# Power_Regulation.net
KiCad netlist of a schematic drawn in Altium Designer
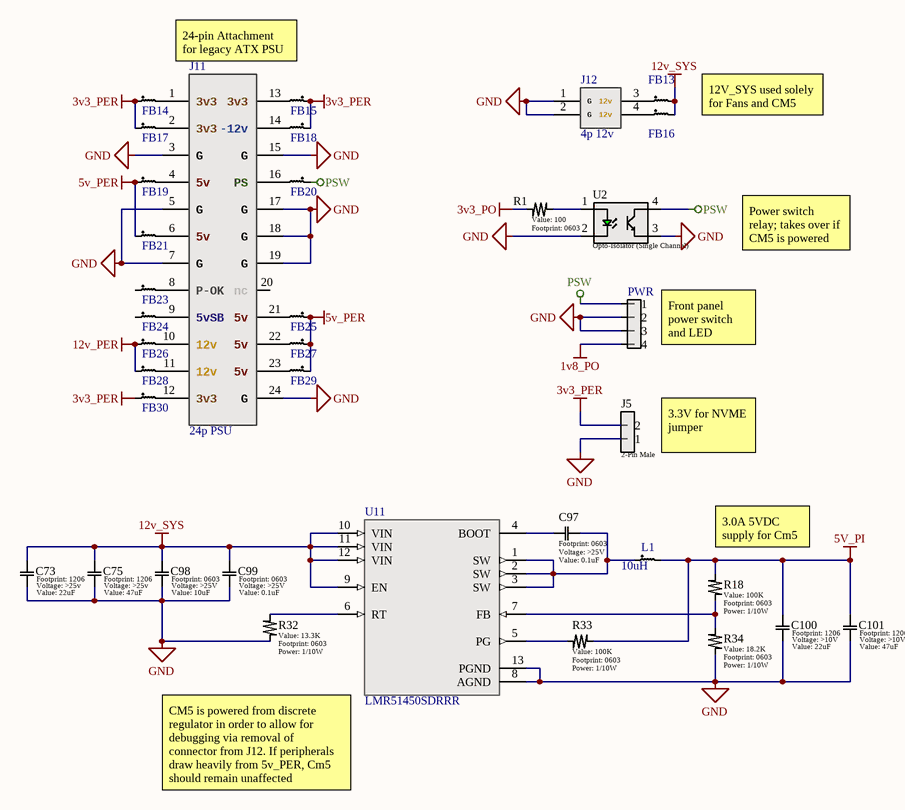
[diagram p0: Power_Regulation.SchDoc]

(export (version "E")
  (design (tool "Eeschema 10.0.6"))
  (components
    (comp (ref "C73")
      (value "22uF")
      (footprint "1206")
      (fields
        (field (name "VOLTAGE") ">25v")
        (field (name "TOLERANCE") "20%")
        (field (name "Comment") "Generic Capacitor")
      )
      (libsource (lib "Capacitors") (part "Generic Capacitor"))
    )
    (comp (ref "C75")
      (value "47uF")
      (footprint "1206")
      (fields
        (field (name "VOLTAGE") ">25v")
        (field (name "TOLERANCE") "20%")
        (field (name "Comment") "Generic Capacitor")
      )
      (libsource (lib "Capacitors") (part "Generic Capacitor"))
    )
    (comp (ref "C97")
      (value "0.1uF")
      (footprint "0603")
      (fields
        (field (name "VOLTAGE") ">25V")
        (field (name "TOLERANCE") "10%")
        (field (name "Comment") "Generic Capacitor")
      )
      (libsource (lib "Capacitors") (part "Generic Capacitor"))
    )
    (comp (ref "C98")
      (value "10uF")
      (footprint "0603")
      (fields
        (field (name "VOLTAGE") ">25V")
        (field (name "TOLERANCE") "10%")
        (field (name "Comment") "Generic Capacitor")
      )
      (libsource (lib "Capacitors") (part "Generic Capacitor"))
    )
    (comp (ref "C99")
      (value "0.1uF")
      (footprint "0603")
      (fields
        (field (name "VOLTAGE") ">25V")
        (field (name "TOLERANCE") "10%")
        (field (name "Comment") "Generic Capacitor")
      )
      (libsource (lib "Capacitors") (part "Generic Capacitor"))
    )
    (comp (ref "C100")
      (value "22uF")
      (footprint "1206")
      (fields
        (field (name "VOLTAGE") ">10V")
        (field (name "TOLERANCE") "20%")
        (field (name "Comment") "Generic Capacitor")
      )
      (libsource (lib "Capacitors") (part "Generic Capacitor"))
    )
    (comp (ref "C101")
      (value "47uF")
      (footprint "1206")
      (fields
        (field (name "VOLTAGE") ">10V")
        (field (name "TOLERANCE") "10%")
        (field (name "Comment") "Generic Capacitor")
      )
      (libsource (lib "Capacitors") (part "Generic Capacitor"))
    )
    (comp (ref "FB13")
      (value "1206 Ferrite")
      (footprint "1206")
      (description "160 Ohms @ 100MHz 1 Power, Signal Line Ferrite Bead 1206 (3216 Metric) 6A 18mOhm")
      (libsource (lib "Inductors") (part "HI1206T161R-10"))
    )
    (comp (ref "FB14")
      (value "1206 Ferrite")
      (footprint "1206")
      (description "160 Ohms @ 100MHz 1 Power, Signal Line Ferrite Bead 1206 (3216 Metric) 6A 18mOhm")
      (libsource (lib "Inductors") (part "HI1206T161R-10"))
    )
    (comp (ref "FB15")
      (value "1206 Ferrite")
      (footprint "1206")
      (description "160 Ohms @ 100MHz 1 Power, Signal Line Ferrite Bead 1206 (3216 Metric) 6A 18mOhm")
      (libsource (lib "") (part "HI1206T161R-10_1"))
    )
    (comp (ref "FB16")
      (value "1206 Ferrite")
      (footprint "1206")
      (description "160 Ohms @ 100MHz 1 Power, Signal Line Ferrite Bead 1206 (3216 Metric) 6A 18mOhm")
      (libsource (lib "Inductors") (part "HI1206T161R-10"))
    )
    (comp (ref "FB17")
      (value "1206 Ferrite")
      (footprint "1206")
      (description "160 Ohms @ 100MHz 1 Power, Signal Line Ferrite Bead 1206 (3216 Metric) 6A 18mOhm")
      (libsource (lib "Inductors") (part "HI1206T161R-10"))
    )
    (comp (ref "FB18")
      (value "1206 Ferrite")
      (footprint "1206")
      (description "160 Ohms @ 100MHz 1 Power, Signal Line Ferrite Bead 1206 (3216 Metric) 6A 18mOhm")
      (libsource (lib "") (part "HI1206T161R-10_1"))
    )
    (comp (ref "FB19")
      (value "1206 Ferrite")
      (footprint "1206")
      (description "160 Ohms @ 100MHz 1 Power, Signal Line Ferrite Bead 1206 (3216 Metric) 6A 18mOhm")
      (libsource (lib "Inductors") (part "HI1206T161R-10"))
    )
    (comp (ref "FB20")
      (value "1206 Ferrite")
      (footprint "1206")
      (description "160 Ohms @ 100MHz 1 Power, Signal Line Ferrite Bead 1206 (3216 Metric) 6A 18mOhm")
      (libsource (lib "") (part "HI1206T161R-10_1"))
    )
    (comp (ref "FB21")
      (value "1206 Ferrite")
      (footprint "1206")
      (description "160 Ohms @ 100MHz 1 Power, Signal Line Ferrite Bead 1206 (3216 Metric) 6A 18mOhm")
      (libsource (lib "Inductors") (part "HI1206T161R-10"))
    )
    (comp (ref "FB23")
      (value "1206 Ferrite")
      (footprint "1206")
      (description "160 Ohms @ 100MHz 1 Power, Signal Line Ferrite Bead 1206 (3216 Metric) 6A 18mOhm")
      (libsource (lib "Inductors") (part "HI1206T161R-10"))
    )
    (comp (ref "FB24")
      (value "1206 Ferrite")
      (footprint "1206")
      (description "160 Ohms @ 100MHz 1 Power, Signal Line Ferrite Bead 1206 (3216 Metric) 6A 18mOhm")
      (libsource (lib "Inductors") (part "HI1206T161R-10"))
    )
    (comp (ref "FB25")
      (value "1206 Ferrite")
      (footprint "1206")
      (description "160 Ohms @ 100MHz 1 Power, Signal Line Ferrite Bead 1206 (3216 Metric) 6A 18mOhm")
      (libsource (lib "") (part "HI1206T161R-10_1"))
    )
    (comp (ref "FB26")
      (value "1206 Ferrite")
      (footprint "1206")
      (description "160 Ohms @ 100MHz 1 Power, Signal Line Ferrite Bead 1206 (3216 Metric) 6A 18mOhm")
      (libsource (lib "Inductors") (part "HI1206T161R-10"))
    )
    (comp (ref "FB27")
      (value "1206 Ferrite")
      (footprint "1206")
      (description "160 Ohms @ 100MHz 1 Power, Signal Line Ferrite Bead 1206 (3216 Metric) 6A 18mOhm")
      (libsource (lib "") (part "HI1206T161R-10_1"))
    )
    (comp (ref "FB28")
      (value "1206 Ferrite")
      (footprint "1206")
      (description "160 Ohms @ 100MHz 1 Power, Signal Line Ferrite Bead 1206 (3216 Metric) 6A 18mOhm")
      (libsource (lib "Inductors") (part "HI1206T161R-10"))
    )
    (comp (ref "FB29")
      (value "1206 Ferrite")
      (footprint "1206")
      (description "160 Ohms @ 100MHz 1 Power, Signal Line Ferrite Bead 1206 (3216 Metric) 6A 18mOhm")
      (libsource (lib "") (part "HI1206T161R-10_1"))
    )
    (comp (ref "FB30")
      (value "1206 Ferrite")
      (footprint "1206")
      (description "160 Ohms @ 100MHz 1 Power, Signal Line Ferrite Bead 1206 (3216 Metric) 6A 18mOhm")
      (libsource (lib "Inductors") (part "HI1206T161R-10"))
    )
    (comp (ref "J5")
      (value "2-Pin Male")
      (footprint "0022057025")
      (description "Conn Shrouded Header (4 Sides) HDR 2 POS 2.5mm Solder RA Thru-Hole SPOX™ Bag")
      (libsource (lib "Connectors") (part "0022057025"))
    )
    (comp (ref "J11")
      (value "24p PSU")
      (footprint "CONN_442060007_MOL")
      (description "Connector Header Through Hole 24 position 0.165\" (4.20mm)")
      (libsource (lib "Connectors") (part "442060007"))
    )
    (comp (ref "J12")
      (value "4p 12v")
      (footprint "CON_39281043")
      (description "Connector Header Through Hole 4 position 0.165\" (4.20mm)")
      (libsource (lib "Connectors") (part "39281043"))
    )
    (comp (ref "L1")
      (value "10uH")
      (footprint "SMD 8.2x8.6mm")
      (description "5.1A 10uH ±20% 5.2A - Power Inductor")
      (fields
        (field (name "MANUFACTURER_PART_NUMBER") "IHLP3232DZER100M5A")
        (field (name "COPYRIGHT") "Copyright (C) 2023 Ultra Librarian. All rights reserved.")
      )
      (libsource (lib "Inductors") (part "IHLP3232DZER100M5A"))
    )
    (comp (ref "PWR")
      (value "4-Pin Male Header (0.100\" Pitch)")
      (footprint "TSW-104-07-T-S")
      (description "Connector Header Through Hole 4 position 0.100\" (2.54mm)")
      (libsource (lib "Connectors") (part "TSW-104-07-T-S"))
    )
    (comp (ref "R1")
      (value "100")
      (footprint "0603")
      (fields
        (field (name "TOLERANCE") "1%")
        (field (name "POWER") "1/10W")
        (field (name "Comment") "Generic Resistor")
      )
      (libsource (lib "Resistors") (part "Generic Resistor"))
    )
    (comp (ref "R18")
      (value "100K")
      (footprint "0603")
      (fields
        (field (name "TOLERANCE") "1%")
        (field (name "POWER") "1/10W")
        (field (name "Comment") "Generic Resistor")
      )
      (libsource (lib "Resistors") (part "Generic Resistor"))
    )
    (comp (ref "R32")
      (value "13.3K")
      (footprint "0603")
      (fields
        (field (name "TOLERANCE") "1%")
        (field (name "POWER") "1/10W")
        (field (name "Comment") "Generic Resistor")
      )
      (libsource (lib "Resistors") (part "Generic Resistor"))
    )
    (comp (ref "R33")
      (value "100K")
      (footprint "0603")
      (fields
        (field (name "TOLERANCE") "1%")
        (field (name "POWER") "1/10W")
        (field (name "Comment") "Generic Resistor")
      )
      (libsource (lib "Resistors") (part "Generic Resistor"))
    )
    (comp (ref "R34")
      (value "18.2K")
      (footprint "0603")
      (fields
        (field (name "TOLERANCE") "1%")
        (field (name "POWER") "1/10W")
        (field (name "Comment") "Generic Resistor")
      )
      (libsource (lib "Resistors") (part "Generic Resistor"))
    )
    (comp (ref "U2")
      (value "Opto-Isolator (Single Channel)")
      (footprint "4-SMD (7.62mm Gull-Wing) Opto-Transistor")
      (description "LTV Series Single Channel 80 V 5000 Vrms Transistor Output Optocoupler SMT-DIP-4")
      (fields
        (field (name "MANUFACTURER") "Vishay Lite-On")
        (field (name "MANUFACTURER PART NUMBER") "LTV-816S-TA1")
      )
      (libsource (lib "Switches") (part "LTV-816S"))
    )
    (comp (ref "U11")
      (value "LMR51450SDRRR")
      (footprint "WSON-12")
      (description "36-V, 5-A synchronous buck converter")
      (fields (field (name "MF") "Texas Instruments"))
      (libsource (lib "Regulators") (part "LMR51450SDRRR"))
    )
  )
  (nets
    (net (code "1") (name "1v8_PO") (class "Default")
      (node (ref "PWR") (pin "4") (pinfunction "4_4") (pintype "passive"))
    )
    (net (code "2") (name "3v3_PER") (class "Default")
      (node (ref "FB14") (pin "1") (pinfunction "1_1") (pintype "passive"))
      (node (ref "FB15") (pin "1") (pinfunction "1_1") (pintype "passive"))
      (node (ref "FB17") (pin "1") (pinfunction "1_1") (pintype "passive"))
      (node (ref "FB18") (pin "1") (pinfunction "1_1") (pintype "passive"))
      (node (ref "FB30") (pin "1") (pinfunction "1_1") (pintype "passive"))
      (node (ref "J5") (pin "2") (pinfunction "2_2") (pintype "passive"))
    )
    (net (code "3") (name "3v3_PO") (class "Default")
      (node (ref "R1") (pin "1") (pinfunction "1_1") (pintype "passive"))
    )
    (net (code "4") (name "5V_PI") (class "Default")
      (node (ref "C100") (pin "1") (pinfunction "1_1") (pintype "passive"))
      (node (ref "C101") (pin "1") (pinfunction "1_1") (pintype "passive"))
      (node (ref "L1") (pin "2") (pinfunction "2_2") (pintype "passive"))
      (node (ref "R18") (pin "2") (pinfunction "2_2") (pintype "passive"))
      (node (ref "R33") (pin "1") (pinfunction "1_1") (pintype "passive"))
    )
    (net (code "5") (name "5v_PER") (class "Default")
      (node (ref "FB19") (pin "1") (pinfunction "1_1") (pintype "passive"))
      (node (ref "FB21") (pin "1") (pinfunction "1_1") (pintype "passive"))
      (node (ref "FB25") (pin "1") (pinfunction "1_1") (pintype "passive"))
      (node (ref "FB27") (pin "1") (pinfunction "1_1") (pintype "passive"))
      (node (ref "FB29") (pin "1") (pinfunction "1_1") (pintype "passive"))
    )
    (net (code "6") (name "12v_PER") (class "Default")
      (node (ref "FB26") (pin "1") (pinfunction "1_1") (pintype "passive"))
      (node (ref "FB28") (pin "1") (pinfunction "1_1") (pintype "passive"))
    )
    (net (code "7") (name "12v_SYS") (class "Default")
      (node (ref "C73") (pin "1") (pinfunction "1_1") (pintype "passive"))
      (node (ref "C75") (pin "1") (pinfunction "1_1") (pintype "passive"))
      (node (ref "C98") (pin "1") (pinfunction "1_1") (pintype "passive"))
      (node (ref "C99") (pin "1") (pinfunction "1_1") (pintype "passive"))
      (node (ref "FB13") (pin "2") (pinfunction "2_2") (pintype "passive"))
      (node (ref "FB16") (pin "2") (pinfunction "2_2") (pintype "passive"))
      (node (ref "U11") (pin "10") (pinfunction "VIN_10") (pintype "input"))
      (node (ref "U11") (pin "11") (pinfunction "VIN_11") (pintype "input"))
      (node (ref "U11") (pin "12") (pinfunction "VIN_12") (pintype "input"))
      (node (ref "U11") (pin "9") (pinfunction "EN_9") (pintype "input"))
    )
    (net (code "8") (name "GND") (class "Default")
      (node (ref "C100") (pin "2") (pinfunction "2_2") (pintype "passive"))
      (node (ref "C101") (pin "2") (pinfunction "2_2") (pintype "passive"))
      (node (ref "C73") (pin "2") (pinfunction "2_2") (pintype "passive"))
      (node (ref "C75") (pin "2") (pinfunction "2_2") (pintype "passive"))
      (node (ref "C98") (pin "2") (pinfunction "2_2") (pintype "passive"))
      (node (ref "C99") (pin "2") (pinfunction "2_2") (pintype "passive"))
      (node (ref "J11") (pin "15") (pinfunction "G_15") (pintype "passive"))
      (node (ref "J11") (pin "17") (pinfunction "G_17") (pintype "passive"))
      (node (ref "J11") (pin "18") (pinfunction "G_18") (pintype "passive"))
      (node (ref "J11") (pin "19") (pinfunction "G_19") (pintype "passive"))
      (node (ref "J11") (pin "24") (pinfunction "G_24") (pintype "passive"))
      (node (ref "J11") (pin "3") (pinfunction "G_3") (pintype "passive"))
      (node (ref "J11") (pin "5") (pinfunction "G_5") (pintype "passive"))
      (node (ref "J11") (pin "7") (pinfunction "G_7") (pintype "passive"))
      (node (ref "J12") (pin "1") (pinfunction "G_1") (pintype "passive"))
      (node (ref "J12") (pin "2") (pinfunction "G_2") (pintype "passive"))
      (node (ref "J5") (pin "1") (pinfunction "1_1") (pintype "passive"))
      (node (ref "PWR") (pin "2") (pinfunction "2_2") (pintype "passive"))
      (node (ref "PWR") (pin "3") (pinfunction "3_3") (pintype "passive"))
      (node (ref "R32") (pin "1") (pinfunction "1_1") (pintype "passive"))
      (node (ref "R34") (pin "1") (pinfunction "1_1") (pintype "passive"))
      (node (ref "U11") (pin "13") (pinfunction "PGND_13") (pintype "power_in"))
      (node (ref "U11") (pin "8") (pinfunction "AGND_8") (pintype "power_in"))
      (node (ref "U2") (pin "2") (pinfunction "2_2") (pintype "passive"))
      (node (ref "U2") (pin "3") (pinfunction "3_3") (pintype "passive"))
    )
    (net (code "9") (name "Net-(C97-Pad2)") (class "Default")
      (node (ref "C97") (pin "2") (pinfunction "2_2") (pintype "passive"))
      (node (ref "L1") (pin "1") (pinfunction "1_1") (pintype "passive"))
      (node (ref "U11") (pin "1") (pinfunction "SW_1") (pintype "output"))
      (node (ref "U11") (pin "2") (pinfunction "SW_2") (pintype "output"))
      (node (ref "U11") (pin "3") (pinfunction "SW_3") (pintype "output"))
    )
    (net (code "10") (name "Net-(FB13-Pad1)") (class "Default")
      (node (ref "FB13") (pin "1") (pinfunction "1_1") (pintype "passive"))
      (node (ref "J12") (pin "3") (pinfunction "12v_3") (pintype "passive"))
    )
    (net (code "11") (name "Net-(FB14-Pad2)") (class "Default")
      (node (ref "FB14") (pin "2") (pinfunction "2_2") (pintype "passive"))
      (node (ref "J11") (pin "1") (pinfunction "3v3_1") (pintype "passive"))
    )
    (net (code "12") (name "Net-(FB15-Pad2)") (class "Default")
      (node (ref "FB15") (pin "2") (pinfunction "2_2") (pintype "passive"))
      (node (ref "J11") (pin "13") (pinfunction "3v3_13") (pintype "passive"))
    )
    (net (code "13") (name "Net-(FB16-Pad1)") (class "Default")
      (node (ref "FB16") (pin "1") (pinfunction "1_1") (pintype "passive"))
      (node (ref "J12") (pin "4") (pinfunction "12v_4") (pintype "passive"))
    )
    (net (code "14") (name "Net-(FB17-Pad2)") (class "Default")
      (node (ref "FB17") (pin "2") (pinfunction "2_2") (pintype "passive"))
      (node (ref "J11") (pin "2") (pinfunction "3v3_2") (pintype "passive"))
    )
    (net (code "15") (name "Net-(FB19-Pad2)") (class "Default")
      (node (ref "FB19") (pin "2") (pinfunction "2_2") (pintype "passive"))
      (node (ref "J11") (pin "4") (pinfunction "5v_4") (pintype "passive"))
    )
    (net (code "16") (name "Net-(FB21-Pad2)") (class "Default")
      (node (ref "FB21") (pin "2") (pinfunction "2_2") (pintype "passive"))
      (node (ref "J11") (pin "6") (pinfunction "5v_6") (pintype "passive"))
    )
    (net (code "17") (name "Net-(FB25-Pad2)") (class "Default")
      (node (ref "FB25") (pin "2") (pinfunction "2_2") (pintype "passive"))
      (node (ref "J11") (pin "21") (pinfunction "5v_21") (pintype "passive"))
    )
    (net (code "18") (name "Net-(FB26-Pad2)") (class "Default")
      (node (ref "FB26") (pin "2") (pinfunction "2_2") (pintype "passive"))
      (node (ref "J11") (pin "10") (pinfunction "12v_10") (pintype "passive"))
    )
    (net (code "19") (name "Net-(FB27-Pad2)") (class "Default")
      (node (ref "FB27") (pin "2") (pinfunction "2_2") (pintype "passive"))
      (node (ref "J11") (pin "22") (pinfunction "5v_22") (pintype "passive"))
    )
    (net (code "20") (name "Net-(FB28-Pad2)") (class "Default")
      (node (ref "FB28") (pin "2") (pinfunction "2_2") (pintype "passive"))
      (node (ref "J11") (pin "11") (pinfunction "12v_11") (pintype "passive"))
    )
    (net (code "21") (name "Net-(FB29-Pad2)") (class "Default")
      (node (ref "FB29") (pin "2") (pinfunction "2_2") (pintype "passive"))
      (node (ref "J11") (pin "23") (pinfunction "5v_23") (pintype "passive"))
    )
    (net (code "22") (name "Net-(FB30-Pad2)") (class "Default")
      (node (ref "FB30") (pin "2") (pinfunction "2_2") (pintype "passive"))
      (node (ref "J11") (pin "12") (pinfunction "3v3_12") (pintype "passive"))
    )
    (net (code "23") (name "Net-(J11--12v)") (class "Default")
      (node (ref "FB18") (pin "2") (pinfunction "2_2") (pintype "passive"))
      (node (ref "J11") (pin "14") (pinfunction "-12v_14") (pintype "passive"))
    )
    (net (code "24") (name "Net-(J11-5vSB)") (class "Default")
      (node (ref "FB24") (pin "2") (pinfunction "2_2") (pintype "passive"))
      (node (ref "J11") (pin "9") (pinfunction "5vSB_9") (pintype "passive"))
    )
    (net (code "25") (name "Net-(J11-P-OK)") (class "Default")
      (node (ref "FB23") (pin "2") (pinfunction "2_2") (pintype "passive"))
      (node (ref "J11") (pin "8") (pinfunction "P-OK_8") (pintype "passive"))
    )
    (net (code "26") (name "Net-(J11-PS)") (class "Default")
      (node (ref "FB20") (pin "2") (pinfunction "2_2") (pintype "passive"))
      (node (ref "J11") (pin "16") (pinfunction "PS_16") (pintype "passive"))
    )
    (net (code "27") (name "Net-(R1-Pad2)") (class "Default")
      (node (ref "R1") (pin "2") (pinfunction "2_2") (pintype "passive"))
      (node (ref "U2") (pin "1") (pinfunction "1_1") (pintype "passive"))
    )
    (net (code "28") (name "Net-(U11-BOOT)") (class "Default")
      (node (ref "C97") (pin "1") (pinfunction "1_1") (pintype "passive"))
      (node (ref "U11") (pin "4") (pinfunction "BOOT_4") (pintype "passive"))
    )
    (net (code "29") (name "Net-(U11-FB)") (class "Default")
      (node (ref "R18") (pin "1") (pinfunction "1_1") (pintype "passive"))
      (node (ref "R34") (pin "2") (pinfunction "2_2") (pintype "passive"))
      (node (ref "U11") (pin "7") (pinfunction "FB_7") (pintype "input"))
    )
    (net (code "30") (name "Net-(U11-PG)") (class "Default")
      (node (ref "R33") (pin "2") (pinfunction "2_2") (pintype "passive"))
      (node (ref "U11") (pin "5") (pinfunction "PG_5") (pintype "output"))
    )
    (net (code "31") (name "Net-(U11-RT)") (class "Default")
      (node (ref "R32") (pin "2") (pinfunction "2_2") (pintype "passive"))
      (node (ref "U11") (pin "6") (pinfunction "RT_6") (pintype "input"))
    )
    (net (code "32") (name "PSW") (class "Default")
      (node (ref "FB20") (pin "1") (pinfunction "1_1") (pintype "passive"))
      (node (ref "PWR") (pin "1") (pinfunction "1_1") (pintype "passive"))
      (node (ref "U2") (pin "4") (pinfunction "4_4") (pintype "passive"))
    )
    (net (code "33") (name "unconnected-(FB23-Pad1)") (class "Default")
      (node (ref "FB23") (pin "1") (pinfunction "1_1") (pintype "passive"))
    )
    (net (code "34") (name "unconnected-(FB24-Pad1)") (class "Default")
      (node (ref "FB24") (pin "1") (pinfunction "1_1") (pintype "passive"))
    )
    (net (code "35") (name "unconnected-(J11-nc-Pad20)") (class "Default")
      (node (ref "J11") (pin "20") (pinfunction "nc_20") (pintype "passive"))
    )
  )
)
